# G-CU.net
KiCad netlist of a schematic drawn in EasyEDA Pro
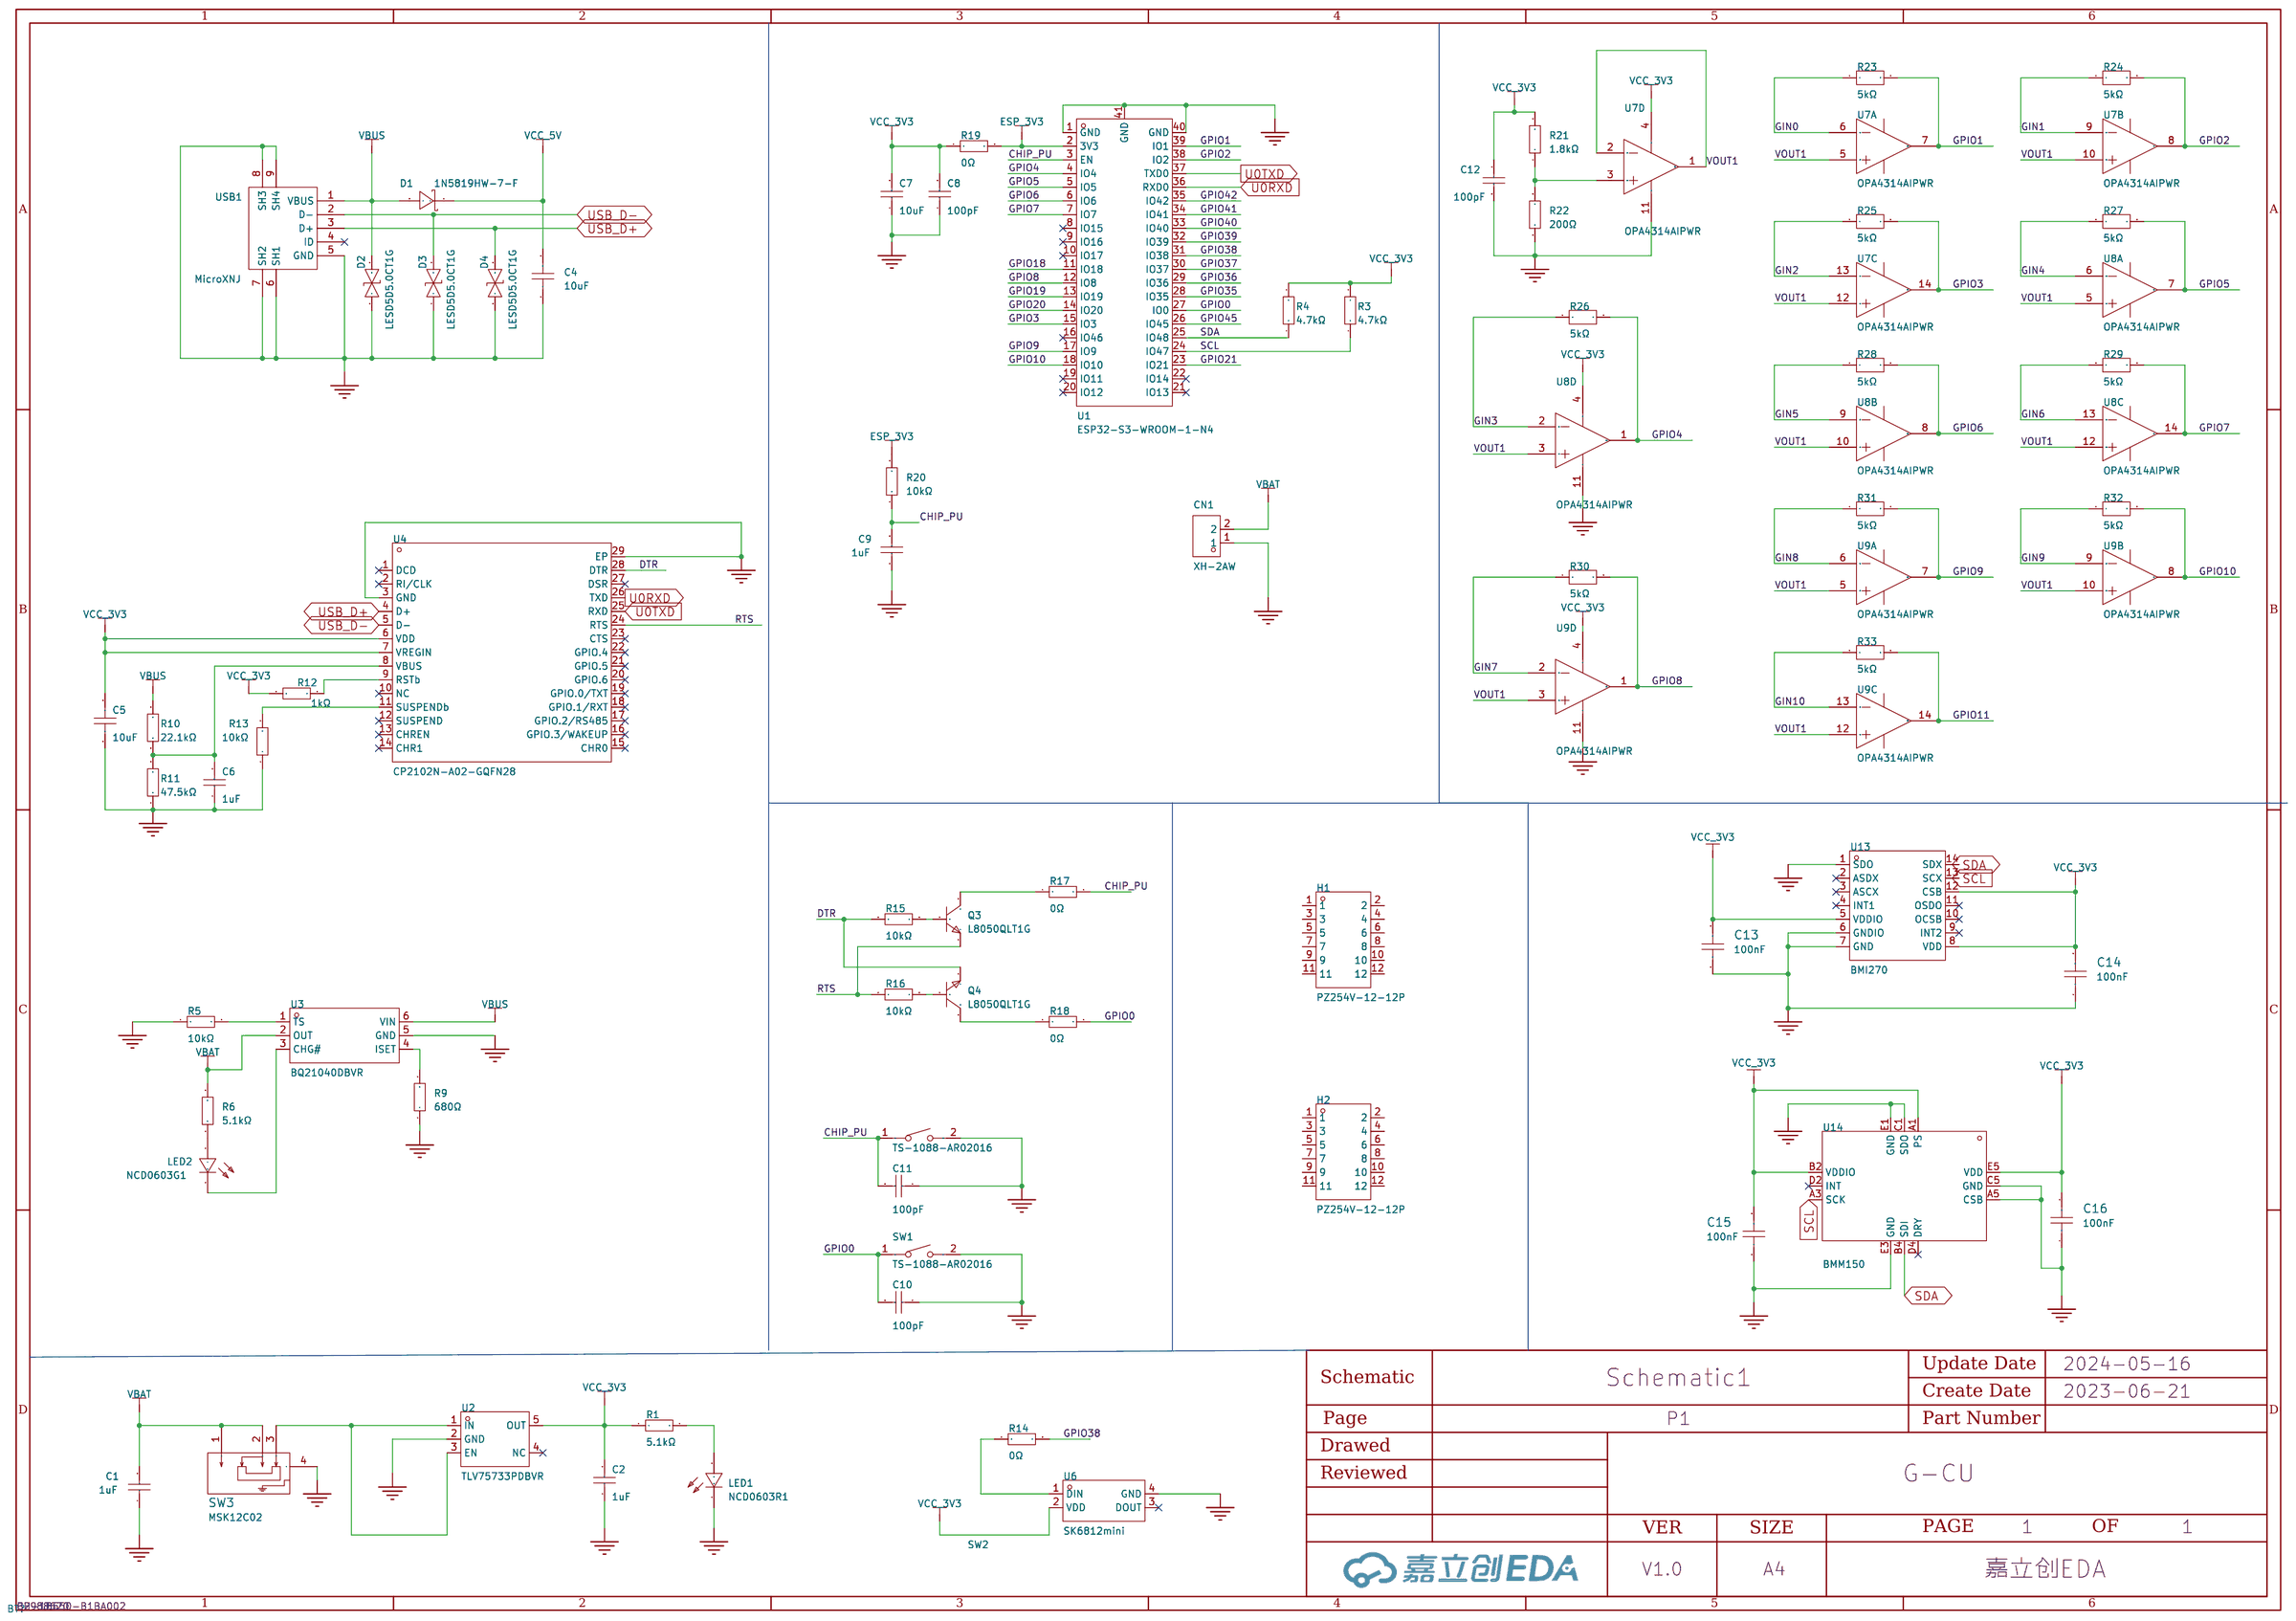
[diagram p0: schematic sheet]

(export (version "E")
  (design (tool "Eeschema 10.0.6"))
  (components
    (comp (ref "C1")
      (value "1uF")
      (footprint "easyedapro:C0402")
      (description "容值:1uF;精度:±10%;额定电压:10V;材质(温度系数):X5R;")
      (fields
        (field (name "Manufacturer Part") "CL05A105KP5NNNC")
        (field (name "Manufacturer") "SAMSUNG(三星)")
      )
      (libsource (lib "easyedapro") (part "CL05A105KP5NNNC"))
    )
    (comp (ref "C2")
      (value "1uF")
      (footprint "easyedapro:C0402")
      (description "容值:1uF;精度:±10%;额定电压:10V;材质(温度系数):X5R;")
      (fields
        (field (name "Manufacturer Part") "CL05A105KP5NNNC")
        (field (name "Manufacturer") "SAMSUNG(三星)")
      )
      (libsource (lib "easyedapro") (part "CL05A105KP5NNNC"))
    )
    (comp (ref "C4")
      (value "10uF")
      (footprint "easyedapro:C0603")
      (description "容值:10uF;精度:±20%;额定电压:25V;材质(温度系数):X5R;")
      (fields
        (field (name "Manufacturer Part") "CL10A106MA8NRNC")
        (field (name "Manufacturer") "SAMSUNG(三星)")
      )
      (libsource (lib "easyedapro") (part "CL10A106MA8NRNC"))
    )
    (comp (ref "C5")
      (value "10uF")
      (footprint "easyedapro:C0603")
      (description "容值:10uF;精度:±20%;额定电压:25V;材质(温度系数):X5R;")
      (fields
        (field (name "Manufacturer Part") "CL10A106MA8NRNC")
        (field (name "Manufacturer") "SAMSUNG(三星)")
      )
      (libsource (lib "easyedapro") (part "CL10A106MA8NRNC"))
    )
    (comp (ref "C6")
      (value "1uF")
      (footprint "easyedapro:C0603")
      (description "容值:1uF;精度:±10%;额定电压:16V;材质(温度系数):X5R;")
      (fields
        (field (name "Manufacturer Part") "CL10A105KO8NNNC")
        (field (name "Manufacturer") "SAMSUNG(三星)")
      )
      (libsource (lib "easyedapro") (part "CL10A105KO8NNNC"))
    )
    (comp (ref "C7")
      (value "10uF")
      (footprint "easyedapro:C0402")
      (description "容值:10uF;精度:±20%;额定电压:6.3V;材质(温度系数):X5R;")
      (fields
        (field (name "Manufacturer Part") "CL05A106MQ5NUNC")
        (field (name "Manufacturer") "SAMSUNG(三星)")
      )
      (libsource (lib "easyedapro") (part "CL05A106MQ5NUNC"))
    )
    (comp (ref "C8")
      (value "100pF")
      (footprint "easyedapro:C0402")
      (description "容值:100pF;精度:±5%;额定电压:50V;材质(温度系数):C0G;")
      (fields (field (name "Manufacturer Part") "0402CG101J500NT") (field (name "Manufacturer") "FH(风华)"))
      (libsource (lib "easyedapro") (part "0402CG101J500NT"))
    )
    (comp (ref "C9")
      (value "1uF")
      (footprint "easyedapro:C0402")
      (description "容值:1uF;精度:±10%;额定电压:10V;材质(温度系数):X5R;")
      (fields
        (field (name "Manufacturer Part") "CL05A105KP5NNNC")
        (field (name "Manufacturer") "SAMSUNG(三星)")
      )
      (libsource (lib "easyedapro") (part "CL05A105KP5NNNC"))
    )
    (comp (ref "C10")
      (value "100pF")
      (footprint "easyedapro:C0402")
      (description "容值:100pF;精度:±5%;额定电压:50V;材质(温度系数):C0G;")
      (fields (field (name "Manufacturer Part") "0402CG101J500NT") (field (name "Manufacturer") "FH(风华)"))
      (libsource (lib "easyedapro") (part "0402CG101J500NT"))
    )
    (comp (ref "C11")
      (value "100pF")
      (footprint "easyedapro:C0402")
      (description "容值:100pF;精度:±5%;额定电压:50V;材质(温度系数):C0G;")
      (fields (field (name "Manufacturer Part") "0402CG101J500NT") (field (name "Manufacturer") "FH(风华)"))
      (libsource (lib "easyedapro") (part "0402CG101J500NT"))
    )
    (comp (ref "C12")
      (value "100pF")
      (footprint "easyedapro:C0402")
      (description "容值:100pF;精度:±5%;额定电压:50V;材质(温度系数):C0G;")
      (fields (field (name "Manufacturer Part") "0402CG101J500NT") (field (name "Manufacturer") "FH(风华)"))
      (libsource (lib "easyedapro") (part "0402CG101J500NT"))
    )
    (comp (ref "C13")
      (value "100nF")
      (footprint "easyedapro:C0402")
      (description "容值:100nF;精度:±10%;额定电压:25V;材质(温度系数):X7R;")
      (fields
        (field (name "Manufacturer Part") "FCC0402B104K250AT")
        (field (name "Manufacturer") "FOJAN(富捷)")
      )
      (libsource (lib "easyedapro") (part "FCC0402B104K250AT"))
    )
    (comp (ref "C14")
      (value "100nF")
      (footprint "easyedapro:C0402")
      (description "容值:100nF;精度:±10%;额定电压:25V;材质(温度系数):X7R;")
      (fields
        (field (name "Manufacturer Part") "FCC0402B104K250AT")
        (field (name "Manufacturer") "FOJAN(富捷)")
      )
      (libsource (lib "easyedapro") (part "FCC0402B104K250AT"))
    )
    (comp (ref "C15")
      (value "100nF")
      (footprint "easyedapro:C0402")
      (description "容值:100nF;精度:±10%;额定电压:25V;材质(温度系数):X7R;")
      (fields
        (field (name "Manufacturer Part") "FCC0402B104K250AT")
        (field (name "Manufacturer") "FOJAN(富捷)")
      )
      (libsource (lib "easyedapro") (part "FCC0402B104K250AT"))
    )
    (comp (ref "C16")
      (value "100nF")
      (footprint "easyedapro:C0402")
      (description "容值:100nF;精度:±10%;额定电压:25V;材质(温度系数):X7R;")
      (fields
        (field (name "Manufacturer Part") "FCC0402B104K250AT")
        (field (name "Manufacturer") "FOJAN(富捷)")
      )
      (libsource (lib "easyedapro") (part "FCC0402B104K250AT"))
    )
    (comp (ref "CN1")
      (value "XH-2AW")
      (footprint "easyedapro:CONN-TH_XH-2AW_C2908611")
      (description "参考系列:XH;间距:2.54mm;插针结构:1x2P;排数:1;每排PIN数:2;行距:-;公母:公型插针;安装方式:弯插;额定电流:3A;工作温度范围:-25°C~+85°C;")
      (fields (field (name "Manufacturer") "HCTL(华灿天禄)"))
      (libsource (lib "easyedapro") (part "XH-2AW_C2908611"))
    )
    (comp (ref "D1")
      (value "1N5819HW-7-F")
      (footprint "easyedapro:SOD-123_L2.7-W1.6-LS3.7-RD")
      (description "直流反向耐压(Vr):40V;平均整流电流(Io):1A;正向压降(Vf):450mV@1A;")
      (fields (field (name "Manufacturer") "DIODES(美台)"))
      (libsource (lib "easyedapro") (part "1N5819HW-7-F"))
    )
    (comp (ref "D2")
      (value "LESD5D5.0CT1G")
      (footprint "easyedapro:SOD-523_L1.2-W0.8-LS1.6-BI")
      (description "极性:双向;反向截止电压(Vrwm):5V;击穿电压(VBR):5.6V;钳位电压(Vc)@Ipp:18.6V;")
      (fields (field (name "Manufacturer") "LRC(乐山无线电)"))
      (libsource (lib "easyedapro") (part "LESD5D5.0CT1G"))
    )
    (comp (ref "D3")
      (value "LESD5D5.0CT1G")
      (footprint "easyedapro:SOD-523_L1.2-W0.8-LS1.6-BI")
      (description "极性:双向;反向截止电压(Vrwm):5V;击穿电压(VBR):5.6V;钳位电压(Vc)@Ipp:18.6V;")
      (fields (field (name "Manufacturer") "LRC(乐山无线电)"))
      (libsource (lib "easyedapro") (part "LESD5D5.0CT1G"))
    )
    (comp (ref "D4")
      (value "LESD5D5.0CT1G")
      (footprint "easyedapro:SOD-523_L1.2-W0.8-LS1.6-BI")
      (description "极性:双向;反向截止电压(Vrwm):5V;击穿电压(VBR):5.6V;钳位电压(Vc)@Ipp:18.6V;")
      (fields (field (name "Manufacturer") "LRC(乐山无线电)"))
      (libsource (lib "easyedapro") (part "LESD5D5.0CT1G"))
    )
    (comp (ref "H1")
      (value "PZ254V-12-12P")
      (footprint "easyedapro:HDR-TH_12P-P2.54-V-M-R2-C6-S2.54")
      (fields (field (name "Manufacturer") "XFCN(兴飞)"))
      (libsource (lib "easyedapro") (part "PZ254V-12-12P"))
    )
    (comp (ref "H2")
      (value "PZ254V-12-12P")
      (footprint "easyedapro:HDR-TH_12P-P2.54-V-M-R2-C6-S2.54")
      (fields (field (name "Manufacturer") "XFCN(兴飞)"))
      (libsource (lib "easyedapro") (part "PZ254V-12-12P"))
    )
    (comp (ref "LED1")
      (value "NCD0603R1")
      (footprint "easyedapro:LED0603-RD_RED")
      (description "发光颜色:红灯;")
      (fields (field (name "Manufacturer") "国星光电"))
      (libsource (lib "easyedapro") (part "FC-DA1608HRK-620D"))
    )
    (comp (ref "LED2")
      (value "NCD0603G1")
      (footprint "easyedapro:LED0603-RD")
      (description "发光颜色:翠绿;")
      (fields (field (name "Manufacturer") "国星光电"))
      (libsource (lib "easyedapro") (part "FC-D1608UGK-520D10"))
    )
    (comp (ref "Q3")
      (value "L8050QLT1G")
      (footprint "easyedapro:SOT-23-3_L2.9-W1.3-P1.90-LS2.4-BR")
      (description "晶体管类型:NPN;集射极击穿电压(Vceo):25V;集电极电流(Ic):800mA;功率(Pd):225mW;")
      (fields (field (name "Manufacturer") "LRC(乐山无线电)"))
      (libsource (lib "easyedapro") (part "L8050QLT1G"))
    )
    (comp (ref "Q4")
      (value "L8050QLT1G")
      (footprint "easyedapro:SOT-23-3_L2.9-W1.3-P1.90-LS2.4-BR")
      (description "晶体管类型:NPN;集射极击穿电压(Vceo):25V;集电极电流(Ic):800mA;功率(Pd):225mW;")
      (fields (field (name "Manufacturer") "LRC(乐山无线电)"))
      (libsource (lib "easyedapro") (part "L8050QLT1G"))
    )
    (comp (ref "R1")
      (value "5.1kΩ")
      (footprint "easyedapro:R0402")
      (description "电阻类型:厚膜电阻;阻值:5.1kΩ;精度:±1%;功率:62.5mW;")
      (fields
        (field (name "Manufacturer Part") "0402WGF5101TCE")
        (field (name "Manufacturer") "UNI-ROYAL(厚声)")
      )
      (libsource (lib "easyedapro") (part "0402WGF5101TCE"))
    )
    (comp (ref "R3")
      (value "4.7kΩ")
      (footprint "easyedapro:R0402")
      (description "电阻类型:厚膜电阻;阻值:4.7kΩ;精度:±1%;功率:62.5mW;")
      (fields
        (field (name "Manufacturer Part") "0402WGF4701TCE")
        (field (name "Manufacturer") "UNI-ROYAL(厚声)")
      )
      (libsource (lib "easyedapro") (part "0402WGF4701TCE"))
    )
    (comp (ref "R4")
      (value "4.7kΩ")
      (footprint "easyedapro:R0402")
      (description "电阻类型:厚膜电阻;阻值:4.7kΩ;精度:±1%;功率:62.5mW;")
      (fields
        (field (name "Manufacturer Part") "0402WGF4701TCE")
        (field (name "Manufacturer") "UNI-ROYAL(厚声)")
      )
      (libsource (lib "easyedapro") (part "0402WGF4701TCE"))
    )
    (comp (ref "R5")
      (value "10kΩ")
      (footprint "easyedapro:R0402")
      (description "电阻类型:厚膜电阻;阻值:10kΩ;精度:±1%;功率:62.5mW;")
      (fields
        (field (name "Manufacturer Part") "0402WGF1002TCE")
        (field (name "Manufacturer") "UNI-ROYAL(厚声)")
      )
      (libsource (lib "easyedapro") (part "0402WGF1002TCE"))
    )
    (comp (ref "R6")
      (value "5.1kΩ")
      (footprint "easyedapro:R0402")
      (description "电阻类型:厚膜电阻;阻值:5.1kΩ;精度:±1%;功率:62.5mW;")
      (fields
        (field (name "Manufacturer Part") "0402WGF5101TCE")
        (field (name "Manufacturer") "UNI-ROYAL(厚声)")
      )
      (libsource (lib "easyedapro") (part "0402WGF5101TCE"))
    )
    (comp (ref "R9")
      (value "680Ω")
      (footprint "easyedapro:R0402")
      (description "电阻类型:厚膜电阻;阻值:680Ω;精度:±1%;功率:62.5mW;")
      (fields
        (field (name "Manufacturer Part") "0402WGF6800TCE")
        (field (name "Manufacturer") "UNI-ROYAL(厚声)")
      )
      (libsource (lib "easyedapro") (part "0402WGF6800TCE"))
    )
    (comp (ref "R10")
      (value "22.1kΩ")
      (footprint "easyedapro:R0402")
      (description "电阻类型:厚膜电阻;阻值:22.1kΩ;精度:±1%;功率:62.5mW;")
      (fields
        (field (name "Manufacturer Part") "0402WGF2212TCE")
        (field (name "Manufacturer") "UNI-ROYAL(厚声)")
      )
      (libsource (lib "easyedapro") (part "0402WGF2212TCE"))
    )
    (comp (ref "R11")
      (value "47.5kΩ")
      (footprint "easyedapro:R0402")
      (description "电阻类型:厚膜电阻;阻值:47.5kΩ;精度:±1%;功率:62.5mW;")
      (fields
        (field (name "Manufacturer Part") "0402WGF4752TCE")
        (field (name "Manufacturer") "UNI-ROYAL(厚声)")
      )
      (libsource (lib "easyedapro") (part "0402WGF4752TCE"))
    )
    (comp (ref "R12")
      (value "1kΩ")
      (footprint "easyedapro:R0402")
      (description "电阻类型:厚膜电阻;阻值:1kΩ;精度:±1%;功率:62.5mW;")
      (fields
        (field (name "Manufacturer Part") "0402WGF1001TCE")
        (field (name "Manufacturer") "UNI-ROYAL(厚声)")
      )
      (libsource (lib "easyedapro") (part "0402WGF1001TCE"))
    )
    (comp (ref "R13")
      (value "10kΩ")
      (footprint "easyedapro:R0402")
      (description "电阻类型:厚膜电阻;阻值:10kΩ;精度:±1%;功率:62.5mW;")
      (fields
        (field (name "Manufacturer Part") "0402WGF1002TCE")
        (field (name "Manufacturer") "UNI-ROYAL(厚声)")
      )
      (libsource (lib "easyedapro") (part "0402WGF1002TCE"))
    )
    (comp (ref "R14")
      (value "0Ω")
      (footprint "easyedapro:R0402")
      (description "电阻类型:厚膜电阻;阻值:0Ω;精度:±5%;功率:62.5mW;")
      (fields
        (field (name "Manufacturer Part") "0402WGJ0000TCE")
        (field (name "Manufacturer") "UNI-ROYAL(厚声)")
      )
      (libsource (lib "easyedapro") (part "0402WGJ0000TCE"))
    )
    (comp (ref "R15")
      (value "10kΩ")
      (footprint "easyedapro:R0402")
      (description "电阻类型:厚膜电阻;阻值:10kΩ;精度:±1%;功率:62.5mW;")
      (fields
        (field (name "Manufacturer Part") "0402WGF1002TCE")
        (field (name "Manufacturer") "UNI-ROYAL(厚声)")
      )
      (libsource (lib "easyedapro") (part "0402WGF1002TCE"))
    )
    (comp (ref "R16")
      (value "10kΩ")
      (footprint "easyedapro:R0402")
      (description "电阻类型:厚膜电阻;阻值:10kΩ;精度:±1%;功率:62.5mW;")
      (fields
        (field (name "Manufacturer Part") "0402WGF1002TCE")
        (field (name "Manufacturer") "UNI-ROYAL(厚声)")
      )
      (libsource (lib "easyedapro") (part "0402WGF1002TCE"))
    )
    (comp (ref "R17")
      (value "0Ω")
      (footprint "easyedapro:R0402")
      (description "电阻类型:厚膜电阻;阻值:0Ω;精度:±5%;功率:62.5mW;")
      (fields
        (field (name "Manufacturer Part") "0402WGJ0000TCE")
        (field (name "Manufacturer") "UNI-ROYAL(厚声)")
      )
      (libsource (lib "easyedapro") (part "0402WGJ0000TCE"))
    )
    (comp (ref "R18")
      (value "0Ω")
      (footprint "easyedapro:R0402")
      (description "电阻类型:厚膜电阻;阻值:0Ω;精度:±5%;功率:62.5mW;")
      (fields
        (field (name "Manufacturer Part") "0402WGJ0000TCE")
        (field (name "Manufacturer") "UNI-ROYAL(厚声)")
      )
      (libsource (lib "easyedapro") (part "0402WGJ0000TCE"))
    )
    (comp (ref "R19")
      (value "0Ω")
      (footprint "easyedapro:R0402")
      (description "电阻类型:厚膜电阻;阻值:0Ω;精度:±5%;功率:62.5mW;")
      (fields
        (field (name "Manufacturer Part") "0402WGJ0000TCE")
        (field (name "Manufacturer") "UNI-ROYAL(厚声)")
      )
      (libsource (lib "easyedapro") (part "0402WGJ0000TCE"))
    )
    (comp (ref "R20")
      (value "10kΩ")
      (footprint "easyedapro:R0402")
      (description "电阻类型:厚膜电阻;阻值:10kΩ;精度:±1%;功率:62.5mW;")
      (fields
        (field (name "Manufacturer Part") "0402WGF1002TCE")
        (field (name "Manufacturer") "UNI-ROYAL(厚声)")
      )
      (libsource (lib "easyedapro") (part "0402WGF1002TCE"))
    )
    (comp (ref "R21")
      (value "1.8kΩ")
      (footprint "easyedapro:R0402")
      (description "电阻类型:厚膜电阻;阻值:1.8kΩ;精度:±1%;功率:62.5mW;")
      (fields
        (field (name "Manufacturer Part") "0402WGF1801TCE")
        (field (name "Manufacturer") "UNI-ROYAL(厚声)")
      )
      (libsource (lib "easyedapro") (part "0402WGF1801TCE"))
    )
    (comp (ref "R22")
      (value "200Ω")
      (footprint "easyedapro:R0402")
      (description "电阻类型:厚膜电阻;阻值:200Ω;精度:±1%;功率:62.5mW;")
      (fields
        (field (name "Manufacturer Part") "0402WGF2000TCE")
        (field (name "Manufacturer") "UNI-ROYAL(厚声)")
      )
      (libsource (lib "easyedapro") (part "0402WGF2000TCE"))
    )
    (comp (ref "R23")
      (value "5kΩ")
      (footprint "easyedapro:R0603")
      (description "电阻类型:薄膜电阻;阻值:5kΩ;精度:±0.1%;功率:100mW;")
      (fields (field (name "Manufacturer Part") "AR03BTCX5001") (field (name "Manufacturer") "Viking(光颉)"))
      (libsource (lib "easyedapro") (part "AR03BTCX5001"))
    )
    (comp (ref "R24")
      (value "5kΩ")
      (footprint "easyedapro:R0603")
      (description "电阻类型:薄膜电阻;阻值:5kΩ;精度:±0.1%;功率:100mW;")
      (fields (field (name "Manufacturer Part") "AR03BTCX5001") (field (name "Manufacturer") "Viking(光颉)"))
      (libsource (lib "easyedapro") (part "AR03BTCX5001"))
    )
    (comp (ref "R25")
      (value "5kΩ")
      (footprint "easyedapro:R0603")
      (description "电阻类型:薄膜电阻;阻值:5kΩ;精度:±0.1%;功率:100mW;")
      (fields (field (name "Manufacturer Part") "AR03BTCX5001") (field (name "Manufacturer") "Viking(光颉)"))
      (libsource (lib "easyedapro") (part "AR03BTCX5001"))
    )
    (comp (ref "R26")
      (value "5kΩ")
      (footprint "easyedapro:R0603")
      (description "电阻类型:薄膜电阻;阻值:5kΩ;精度:±0.1%;功率:100mW;")
      (fields (field (name "Manufacturer Part") "AR03BTCX5001") (field (name "Manufacturer") "Viking(光颉)"))
      (libsource (lib "easyedapro") (part "AR03BTCX5001"))
    )
    (comp (ref "R27")
      (value "5kΩ")
      (footprint "easyedapro:R0603")
      (description "电阻类型:薄膜电阻;阻值:5kΩ;精度:±0.1%;功率:100mW;")
      (fields (field (name "Manufacturer Part") "AR03BTCX5001") (field (name "Manufacturer") "Viking(光颉)"))
      (libsource (lib "easyedapro") (part "AR03BTCX5001"))
    )
    (comp (ref "R28")
      (value "5kΩ")
      (footprint "easyedapro:R0603")
      (description "电阻类型:薄膜电阻;阻值:5kΩ;精度:±0.1%;功率:100mW;")
      (fields (field (name "Manufacturer Part") "AR03BTCX5001") (field (name "Manufacturer") "Viking(光颉)"))
      (libsource (lib "easyedapro") (part "AR03BTCX5001"))
    )
    (comp (ref "R29")
      (value "5kΩ")
      (footprint "easyedapro:R0603")
      (description "电阻类型:薄膜电阻;阻值:5kΩ;精度:±0.1%;功率:100mW;")
      (fields (field (name "Manufacturer Part") "AR03BTCX5001") (field (name "Manufacturer") "Viking(光颉)"))
      (libsource (lib "easyedapro") (part "AR03BTCX5001"))
    )
    (comp (ref "R30")
      (value "5kΩ")
      (footprint "easyedapro:R0603")
      (description "电阻类型:薄膜电阻;阻值:5kΩ;精度:±0.1%;功率:100mW;")
      (fields (field (name "Manufacturer Part") "AR03BTCX5001") (field (name "Manufacturer") "Viking(光颉)"))
      (libsource (lib "easyedapro") (part "AR03BTCX5001"))
    )
    (comp (ref "R31")
      (value "5kΩ")
      (footprint "easyedapro:R0603")
      (description "电阻类型:薄膜电阻;阻值:5kΩ;精度:±0.1%;功率:100mW;")
      (fields (field (name "Manufacturer Part") "AR03BTCX5001") (field (name "Manufacturer") "Viking(光颉)"))
      (libsource (lib "easyedapro") (part "AR03BTCX5001"))
    )
    (comp (ref "R32")
      (value "5kΩ")
      (footprint "easyedapro:R0603")
      (description "电阻类型:薄膜电阻;阻值:5kΩ;精度:±0.1%;功率:100mW;")
      (fields (field (name "Manufacturer Part") "AR03BTCX5001") (field (name "Manufacturer") "Viking(光颉)"))
      (libsource (lib "easyedapro") (part "AR03BTCX5001"))
    )
    (comp (ref "R33")
      (value "5kΩ")
      (footprint "easyedapro:R0603")
      (description "电阻类型:薄膜电阻;阻值:5kΩ;精度:±0.1%;功率:100mW;")
      (fields (field (name "Manufacturer Part") "AR03BTCX5001") (field (name "Manufacturer") "Viking(光颉)"))
      (libsource (lib "easyedapro") (part "AR03BTCX5001"))
    )
    (comp (ref "SW1")
      (value "TS-1088-AR02016")
      (footprint "easyedapro:SW-SMD_L3.9-W3.0-P4.45")
      (description "触点电流:50mA;额定电压(DC):12V;绝缘电阻:100MΩ;电路结构:单刀单掷;安装方式:立贴;作用力:160gf@±50gf;机械寿命:10万次;带支架:否;")
      (fields (field (name "Manufacturer") "XUNPU(讯普)"))
      (libsource (lib "easyedapro") (part "TS-1088-AR02016"))
    )
    (comp (ref "SW2")
      (value "TS-1088-AR02016")
      (footprint "easyedapro:SW-SMD_L3.9-W3.0-P4.45")
      (description "触点电流:50mA;额定电压(DC):12V;绝缘电阻:100MΩ;电路结构:单刀单掷;安装方式:立贴;作用力:160gf@±50gf;机械寿命:10万次;带支架:否;")
      (fields (field (name "Manufacturer") "XUNPU(讯普)"))
      (libsource (lib "easyedapro") (part "TS-1088-AR02016"))
    )
    (comp (ref "SW3")
      (value "MSK12C02")
      (footprint "easyedapro:SW-TH_MSK12C02")
      (fields (field (name "Manufacturer") "SHOU HAN(首韩)"))
      (libsource (lib "easyedapro") (part "MSK12C02"))
    )
    (comp (ref "U1")
      (value "ESP32-S3-WROOM-1-N4")
      (footprint "easyedapro:WIRELM-SMD_ESP32-S3-WROOM-1")
      (fields (field (name "Manufacturer") "ESPRESSIF(乐鑫)"))
      (libsource (lib "easyedapro") (part "ESP32-S3-WROOM-1"))
    )
    (comp (ref "U2")
      (value "TLV75733PDBVR")
      (footprint "easyedapro:SOT-23-5_L2.9-W1.6-P0.95-LS2.8-BL")
      (description "输出类型:固定;输出极性:正;输出通道数:1;最大输入电压:5.5V;输出电压:3.3V;压差:475mV@(1A);输出电流:1A;电源纹波抑制比(PSRR):52dB;")
      (fields (field (name "Manufacturer") "TI(德州仪器)"))
      (libsource (lib "easyedapro") (part "TLV75733PDBVR"))
    )
    (comp (ref "U3")
      (value "BQ21040DBVR")
      (footprint "easyedapro:SOT-23-6_L2.9-W1.6-P0.95-LS2.8-BR")
      (description "电池类型:锂离子/聚合物;电池节数:1;最大充电电流:800mA;电源电压:6.45V;")
      (fields (field (name "Manufacturer") "TI(德州仪器)"))
      (libsource (lib "easyedapro") (part "BQ21040DBVR"))
    )
    (comp (ref "U4")
      (value "CP2102N-A02-GQFN28")
      (footprint "easyedapro:QFN-28_L5.0-W5.0-P0.50-TL-EP3.3")
      (fields (field (name "Manufacturer") "SILICON LABS(芯科)"))
      (libsource (lib "easyedapro") (part "CP2102N-A02-GQFN28"))
    )
    (comp (ref "U6")
      (value "SK6812mini")
      (footprint "easyedapro:LED-SMD_4P-L3.7-W3.5-P1.75-BR-SK6812MINI")
      (fields (field (name "Manufacturer") "欧思科光电"))
      (libsource (lib "easyedapro") (part "SK6812MINI"))
    )
    (comp (ref "U7")
      (value "OPA4314AIPWR")
      (footprint "easyedapro:TSSOP-14_L5.0-W4.4-P0.65-LS6.4-BL")
      (description "OPA4314 四路、3MHz、低功耗、低噪声、RRI/O、1.8V CMOS 运算放大器")
      (fields (field (name "Manufacturer") "TI(德州仪器)"))
      (libsource (lib "easyedapro") (part "OPA4314AIPWR"))
    )
    (comp (ref "U8")
      (value "OPA4314AIPWR")
      (footprint "easyedapro:TSSOP-14_L5.0-W4.4-P0.65-LS6.4-BL")
      (description "OPA4314 四路、3MHz、低功耗、低噪声、RRI/O、1.8V CMOS 运算放大器")
      (fields (field (name "Manufacturer") "TI(德州仪器)"))
      (libsource (lib "easyedapro") (part "OPA4314AIPWR"))
    )
    (comp (ref "U9")
      (value "OPA4314AIPWR")
      (footprint "easyedapro:TSSOP-14_L5.0-W4.4-P0.65-LS6.4-BL")
      (description "OPA4314 四路、3MHz、低功耗、低噪声、RRI/O、1.8V CMOS 运算放大器")
      (fields (field (name "Manufacturer") "TI(德州仪器)"))
      (libsource (lib "easyedapro") (part "OPA4314AIPWR"))
    )
    (comp (ref "U13")
      (value "BMI270")
      (footprint "easyedapro:LGA-14_L3.0-W2.5-P0.50-BR")
      (description "IMU-惯性测量单元")
      (fields (field (name "Manufacturer") "Bosch(博世)"))
      (libsource (lib "easyedapro") (part "BMI270"))
    )
    (comp (ref "U14")
      (value "BMM150")
      (footprint "easyedapro:WLCSP-12_L1.6-W1.6_BMM150")
      (description "磁传感器 3轴磁罗盘")
      (fields (field (name "Manufacturer") "Bosch(博世)"))
      (libsource (lib "easyedapro") (part "BMM150"))
    )
    (comp (ref "USB1")
      (value "MicroXNJ")
      (footprint "easyedapro:MICRO-USB-SMD_MICROXNJ")
      (description "连接器类型:Micro-B;标准:USB 2.0;公母:母座;触点数量:5;端口数量:1;安装方式:卧贴;额定电流 - 电源:1A;工作温度范围:-20°C~+85°C;")
      (fields (field (name "Manufacturer") "SHOU HAN(首韩)"))
      (libsource (lib "easyedapro") (part "MICROXNJ"))
    )
  )
  (nets
    (net (code "1") (name "/CHIP_PU") (class "Default")
      (node (ref "C11") (pin "2") (pinfunction "2_2") (pintype "input"))
      (node (ref "C9") (pin "2") (pinfunction "2_2") (pintype "input"))
      (node (ref "R17") (pin "2") (pinfunction "2_2") (pintype "input"))
      (node (ref "R20") (pin "1") (pinfunction "1_1") (pintype "input"))
      (node (ref "SW2") (pin "1") (pinfunction "1_1") (pintype "input"))
      (node (ref "U1") (pin "3") (pinfunction "EN_3") (pintype "input"))
    )
    (net (code "2") (name "/DTR") (class "Default")
      (node (ref "Q4") (pin "2") (pinfunction "E_2") (pintype "input"))
      (node (ref "R15") (pin "1") (pinfunction "1_1") (pintype "input"))
      (node (ref "U4") (pin "28") (pinfunction "DTR_28") (pintype "input"))
    )
    (net (code "3") (name "/GIN0") (class "Default")
      (node (ref "R23") (pin "1") (pinfunction "1_1") (pintype "input"))
      (node (ref "U7") (pin "6") (pinfunction "IN_B-_6") (pintype "input"))
    )
    (net (code "4") (name "/GIN1") (class "Default")
      (node (ref "R24") (pin "1") (pinfunction "1_1") (pintype "input"))
      (node (ref "U7") (pin "9") (pinfunction "IN_C-_9") (pintype "input"))
    )
    (net (code "5") (name "/GIN2") (class "Default")
      (node (ref "R25") (pin "1") (pinfunction "1_1") (pintype "input"))
      (node (ref "U7") (pin "13") (pinfunction "IN_D-_13") (pintype "input"))
    )
    (net (code "6") (name "/GIN3") (class "Default")
      (node (ref "R26") (pin "1") (pinfunction "1_1") (pintype "input"))
      (node (ref "U8") (pin "2") (pinfunction "IN_A-_2") (pintype "input"))
    )
    (net (code "7") (name "/GIN4") (class "Default")
      (node (ref "R27") (pin "1") (pinfunction "1_1") (pintype "input"))
      (node (ref "U8") (pin "6") (pinfunction "IN_B-_6") (pintype "input"))
    )
    (net (code "8") (name "/GIN5") (class "Default")
      (node (ref "R28") (pin "1") (pinfunction "1_1") (pintype "input"))
      (node (ref "U8") (pin "9") (pinfunction "IN_C-_9") (pintype "input"))
    )
    (net (code "9") (name "/GIN6") (class "Default")
      (node (ref "R29") (pin "1") (pinfunction "1_1") (pintype "input"))
      (node (ref "U8") (pin "13") (pinfunction "IN_D-_13") (pintype "input"))
    )
    (net (code "10") (name "/GIN7") (class "Default")
      (node (ref "R30") (pin "1") (pinfunction "1_1") (pintype "input"))
      (node (ref "U9") (pin "2") (pinfunction "IN_A-_2") (pintype "input"))
    )
    (net (code "11") (name "/GIN8") (class "Default")
      (node (ref "R31") (pin "1") (pinfunction "1_1") (pintype "input"))
      (node (ref "U9") (pin "6") (pinfunction "IN_B-_6") (pintype "input"))
    )
    (net (code "12") (name "/GIN9") (class "Default")
      (node (ref "R32") (pin "1") (pinfunction "1_1") (pintype "input"))
      (node (ref "U9") (pin "9") (pinfunction "IN_C-_9") (pintype "input"))
    )
    (net (code "13") (name "/GIN10") (class "Default")
      (node (ref "R33") (pin "1") (pinfunction "1_1") (pintype "input"))
      (node (ref "U9") (pin "13") (pinfunction "IN_D-_13") (pintype "input"))
    )
    (net (code "14") (name "/GPIO0") (class "Default")
      (node (ref "C10") (pin "2") (pinfunction "2_2") (pintype "input"))
      (node (ref "R18") (pin "2") (pinfunction "2_2") (pintype "input"))
      (node (ref "SW1") (pin "1") (pinfunction "1_1") (pintype "input"))
      (node (ref "U1") (pin "27") (pinfunction "IO0_27") (pintype "input"))
    )
    (net (code "15") (name "/GPIO1") (class "Default")
      (node (ref "R23") (pin "2") (pinfunction "2_2") (pintype "input"))
      (node (ref "U1") (pin "39") (pinfunction "IO1_39") (pintype "input"))
      (node (ref "U7") (pin "7") (pinfunction "OUT_B_7") (pintype "output"))
    )
    (net (code "16") (name "/GPIO2") (class "Default")
      (node (ref "R24") (pin "2") (pinfunction "2_2") (pintype "input"))
      (node (ref "U1") (pin "38") (pinfunction "IO2_38") (pintype "input"))
      (node (ref "U7") (pin "8") (pinfunction "OUT_C_8") (pintype "output"))
    )
    (net (code "17") (name "/GPIO3") (class "Default")
      (node (ref "R25") (pin "2") (pinfunction "2_2") (pintype "input"))
      (node (ref "U1") (pin "15") (pinfunction "IO3_15") (pintype "input"))
      (node (ref "U7") (pin "14") (pinfunction "OUT_D_14") (pintype "output"))
    )
    (net (code "18") (name "/GPIO4") (class "Default")
      (node (ref "R26") (pin "2") (pinfunction "2_2") (pintype "input"))
      (node (ref "U1") (pin "4") (pinfunction "IO4_4") (pintype "input"))
      (node (ref "U8") (pin "1") (pinfunction "OUT_A_1") (pintype "output"))
    )
    (net (code "19") (name "/GPIO5") (class "Default")
      (node (ref "R27") (pin "2") (pinfunction "2_2") (pintype "input"))
      (node (ref "U1") (pin "5") (pinfunction "IO5_5") (pintype "input"))
      (node (ref "U8") (pin "7") (pinfunction "OUT_B_7") (pintype "output"))
    )
    (net (code "20") (name "/GPIO6") (class "Default")
      (node (ref "R28") (pin "2") (pinfunction "2_2") (pintype "input"))
      (node (ref "U1") (pin "6") (pinfunction "IO6_6") (pintype "input"))
      (node (ref "U8") (pin "8") (pinfunction "OUT_C_8") (pintype "output"))
    )
    (net (code "21") (name "/GPIO7") (class "Default")
      (node (ref "R29") (pin "2") (pinfunction "2_2") (pintype "input"))
      (node (ref "U1") (pin "7") (pinfunction "IO7_7") (pintype "input"))
      (node (ref "U8") (pin "14") (pinfunction "OUT_D_14") (pintype "output"))
    )
    (net (code "22") (name "/GPIO8") (class "Default")
      (node (ref "R30") (pin "2") (pinfunction "2_2") (pintype "input"))
      (node (ref "U1") (pin "12") (pinfunction "IO8_12") (pintype "input"))
      (node (ref "U9") (pin "1") (pinfunction "OUT_A_1") (pintype "output"))
    )
    (net (code "23") (name "/GPIO9") (class "Default")
      (node (ref "R31") (pin "2") (pinfunction "2_2") (pintype "input"))
      (node (ref "U1") (pin "17") (pinfunction "IO9_17") (pintype "input"))
      (node (ref "U9") (pin "7") (pinfunction "OUT_B_7") (pintype "output"))
    )
    (net (code "24") (name "/GPIO10") (class "Default")
      (node (ref "R32") (pin "2") (pinfunction "2_2") (pintype "input"))
      (node (ref "U1") (pin "18") (pinfunction "IO10_18") (pintype "input"))
      (node (ref "U9") (pin "8") (pinfunction "OUT_C_8") (pintype "output"))
    )
    (net (code "25") (name "/GPIO11") (class "Default")
      (node (ref "R33") (pin "2") (pinfunction "2_2") (pintype "input"))
      (node (ref "U9") (pin "14") (pinfunction "OUT_D_14") (pintype "output"))
    )
    (net (code "26") (name "/GPIO18") (class "Default")
      (node (ref "U1") (pin "11") (pinfunction "IO18_11") (pintype "input"))
    )
    (net (code "27") (name "/GPIO19") (class "Default")
      (node (ref "U1") (pin "13") (pinfunction "IO19_13") (pintype "input"))
    )
    (net (code "28") (name "/GPIO20") (class "Default")
      (node (ref "U1") (pin "14") (pinfunction "IO20_14") (pintype "input"))
    )
    (net (code "29") (name "/GPIO21") (class "Default")
      (node (ref "U1") (pin "23") (pinfunction "IO21_23") (pintype "input"))
    )
    (net (code "30") (name "/GPIO35") (class "Default")
      (node (ref "U1") (pin "28") (pinfunction "IO35_28") (pintype "input"))
    )
    (net (code "31") (name "/GPIO36") (class "Default")
      (node (ref "U1") (pin "29") (pinfunction "IO36_29") (pintype "input"))
    )
    (net (code "32") (name "/GPIO37") (class "Default")
      (node (ref "U1") (pin "30") (pinfunction "IO37_30") (pintype "input"))
    )
    (net (code "33") (name "/GPIO38") (class "Default")
      (node (ref "R14") (pin "2") (pinfunction "2_2") (pintype "input"))
      (node (ref "U1") (pin "31") (pinfunction "IO38_31") (pintype "input"))
    )
    (net (code "34") (name "/GPIO39") (class "Default")
      (node (ref "U1") (pin "32") (pinfunction "IO39_32") (pintype "input"))
    )
    (net (code "35") (name "/GPIO40") (class "Default")
      (node (ref "U1") (pin "33") (pinfunction "IO40_33") (pintype "input"))
    )
    (net (code "36") (name "/GPIO41") (class "Default")
      (node (ref "U1") (pin "34") (pinfunction "IO41_34") (pintype "input"))
    )
    (net (code "37") (name "/GPIO42") (class "Default")
      (node (ref "U1") (pin "35") (pinfunction "IO42_35") (pintype "input"))
    )
    (net (code "38") (name "/GPIO45") (class "Default")
      (node (ref "U1") (pin "26") (pinfunction "IO45_26") (pintype "input"))
    )
    (net (code "39") (name "/RTS") (class "Default")
      (node (ref "Q3") (pin "2") (pinfunction "E_2") (pintype "input"))
      (node (ref "R16") (pin "1") (pinfunction "1_1") (pintype "input"))
      (node (ref "U4") (pin "24") (pinfunction "RTS_24") (pintype "input"))
    )
    (net (code "40") (name "/VOUT1") (class "Default")
      (node (ref "U7") (pin "1") (pinfunction "OUT_A_1") (pintype "output"))
      (node (ref "U7") (pin "10") (pinfunction "IN_C+_10") (pintype "input"))
      (node (ref "U7") (pin "12") (pinfunction "IN_D+_12") (pintype "input"))
      (node (ref "U7") (pin "2") (pinfunction "IN_A-_2") (pintype "input"))
      (node (ref "U7") (pin "5") (pinfunction "IN_B+_5") (pintype "input"))
      (node (ref "U8") (pin "10") (pinfunction "IN_C+_10") (pintype "input"))
      (node (ref "U8") (pin "12") (pinfunction "IN_D+_12") (pintype "input"))
      (node (ref "U8") (pin "3") (pinfunction "IN_A+_3") (pintype "input"))
      (node (ref "U8") (pin "5") (pinfunction "IN_B+_5") (pintype "input"))
      (node (ref "U9") (pin "10") (pinfunction "IN_C+_10") (pintype "input"))
      (node (ref "U9") (pin "12") (pinfunction "IN_D+_12") (pintype "input"))
      (node (ref "U9") (pin "3") (pinfunction "IN_A+_3") (pintype "input"))
      (node (ref "U9") (pin "5") (pinfunction "IN_B+_5") (pintype "input"))
    )
    (net (code "41") (name "ESP_3V3") (class "Default")
      (node (ref "R19") (pin "2") (pinfunction "2_2") (pintype "input"))
      (node (ref "R20") (pin "2") (pinfunction "2_2") (pintype "input"))
      (node (ref "U1") (pin "2") (pinfunction "3V3_2") (pintype "input"))
    )
    (net (code "42") (name "GND") (class "Default")
      (node (ref "C1") (pin "1") (pinfunction "1_1") (pintype "input"))
      (node (ref "C10") (pin "1") (pinfunction "1_1") (pintype "input"))
      (node (ref "C11") (pin "1") (pinfunction "1_1") (pintype "input"))
      (node (ref "C12") (pin "2") (pinfunction "2_2") (pintype "input"))
      (node (ref "C13") (pin "1") (pinfunction "1_1") (pintype "input"))
      (node (ref "C14") (pin "1") (pinfunction "1_1") (pintype "input"))
      (node (ref "C15") (pin "1") (pinfunction "1_1") (pintype "input"))
      (node (ref "C16") (pin "1") (pinfunction "1_1") (pintype "input"))
      (node (ref "C2") (pin "1") (pinfunction "1_1") (pintype "input"))
      (node (ref "C4") (pin "1") (pinfunction "1_1") (pintype "input"))
      (node (ref "C5") (pin "1") (pinfunction "1_1") (pintype "input"))
      (node (ref "C6") (pin "1") (pinfunction "1_1") (pintype "input"))
      (node (ref "C7") (pin "1") (pinfunction "1_1") (pintype "input"))
      (node (ref "C8") (pin "1") (pinfunction "1_1") (pintype "input"))
      (node (ref "C9") (pin "1") (pinfunction "1_1") (pintype "input"))
      (node (ref "CN1") (pin "1") (pinfunction "1_1") (pintype "input"))
      (node (ref "D2") (pin "1") (pinfunction "1_1") (pintype "input"))
      (node (ref "D3") (pin "1") (pinfunction "1_1") (pintype "input"))
      (node (ref "D4") (pin "1") (pinfunction "1_1") (pintype "input"))
      (node (ref "LED1") (pin "1") (pinfunction "K_1") (pintype "input"))
      (node (ref "R11") (pin "1") (pinfunction "1_1") (pintype "input"))
      (node (ref "R13") (pin "1") (pinfunction "1_1") (pintype "input"))
      (node (ref "R22") (pin "1") (pinfunction "1_1") (pintype "input"))
      (node (ref "R5") (pin "1") (pinfunction "1_1") (pintype "input"))
      (node (ref "R9") (pin "1") (pinfunction "1_1") (pintype "input"))
      (node (ref "SW1") (pin "2") (pinfunction "2_2") (pintype "input"))
      (node (ref "SW2") (pin "2") (pinfunction "2_2") (pintype "input"))
      (node (ref "SW3") (pin "4") (pinfunction "4_4") (pintype "input"))
      (node (ref "U1") (pin "1") (pinfunction "GND_1") (pintype "input"))
      (node (ref "U1") (pin "40") (pinfunction "GND_40") (pintype "input"))
      (node (ref "U1") (pin "41") (pinfunction "GND_41") (pintype "input"))
      (node (ref "U13") (pin "1") (pinfunction "SDO_1") (pintype "input"))
      (node (ref "U13") (pin "6") (pinfunction "GNDIO_6") (pintype "input"))
      (node (ref "U13") (pin "7") (pinfunction "GND_7") (pintype "input"))
      (node (ref "U14") (pin "A5") (pinfunction "CSB_A5") (pintype "input"))
      (node (ref "U14") (pin "C1") (pinfunction "SDO_C1") (pintype "input"))
      (node (ref "U14") (pin "C5") (pinfunction "GND_C5") (pintype "input"))
      (node (ref "U14") (pin "E1") (pinfunction "GND_E1") (pintype "input"))
      (node (ref "U14") (pin "E3") (pinfunction "GND_E3") (pintype "input"))
      (node (ref "U2") (pin "2") (pinfunction "GND_2") (pintype "input"))
      (node (ref "U3") (pin "5") (pinfunction "GND_5") (pintype "input"))
      (node (ref "U4") (pin "29") (pinfunction "EP_29") (pintype "input"))
      (node (ref "U4") (pin "3") (pinfunction "GND_3") (pintype "input"))
      (node (ref "U6") (pin "4") (pinfunction "GND_4") (pintype "input"))
      (node (ref "U7") (pin "11") (pinfunction "V-_11") (pintype "input"))
      (node (ref "U8") (pin "11") (pinfunction "V-_11") (pintype "input"))
      (node (ref "U9") (pin "11") (pinfunction "V-_11") (pintype "input"))
      (node (ref "USB1") (pin "5") (pinfunction "GND_5") (pintype "input"))
      (node (ref "USB1") (pin "6") (pinfunction "SH1_6") (pintype "input"))
      (node (ref "USB1") (pin "7") (pinfunction "SH2_7") (pintype "input"))
      (node (ref "USB1") (pin "8") (pinfunction "SH3_8") (pintype "input"))
      (node (ref "USB1") (pin "9") (pinfunction "SH4_9") (pintype "input"))
    )
    (net (code "43") (name "Net-(LED1-A)") (class "Default")
      (node (ref "LED1") (pin "2") (pinfunction "A_2") (pintype "input"))
      (node (ref "R1") (pin "2") (pinfunction "2_2") (pintype "input"))
    )
    (net (code "44") (name "Net-(LED2-A)") (class "Default")
      (node (ref "LED2") (pin "2") (pinfunction "A_2") (pintype "input"))
      (node (ref "R6") (pin "1") (pinfunction "1_1") (pintype "input"))
    )
    (net (code "45") (name "Net-(LED2-K)") (class "Default")
      (node (ref "LED2") (pin "1") (pinfunction "K_1") (pintype "input"))
      (node (ref "U3") (pin "3") (pinfunction "CHG#_3") (pintype "input"))
    )
    (net (code "46") (name "Net-(Q3-B)") (class "Default")
      (node (ref "Q3") (pin "1") (pinfunction "B_1") (pintype "input"))
      (node (ref "R15") (pin "2") (pinfunction "2_2") (pintype "input"))
    )
    (net (code "47") (name "Net-(Q3-C)") (class "Default")
      (node (ref "Q3") (pin "3") (pinfunction "C_3") (pintype "input"))
      (node (ref "R17") (pin "1") (pinfunction "1_1") (pintype "input"))
    )
    (net (code "48") (name "Net-(Q4-B)") (class "Default")
      (node (ref "Q4") (pin "1") (pinfunction "B_1") (pintype "input"))
      (node (ref "R16") (pin "2") (pinfunction "2_2") (pintype "input"))
    )
    (net (code "49") (name "Net-(Q4-C)") (class "Default")
      (node (ref "Q4") (pin "3") (pinfunction "C_3") (pintype "input"))
      (node (ref "R18") (pin "1") (pinfunction "1_1") (pintype "input"))
    )
    (net (code "50") (name "Net-(U2-EN)") (class "Default")
      (node (ref "SW3") (pin "3") (pinfunction "3_3") (pintype "input"))
      (node (ref "U2") (pin "1") (pinfunction "IN_1") (pintype "input"))
      (node (ref "U2") (pin "3") (pinfunction "EN_3") (pintype "input"))
    )
    (net (code "51") (name "Net-(U3-ISET)") (class "Default")
      (node (ref "R9") (pin "2") (pinfunction "2_2") (pintype "input"))
      (node (ref "U3") (pin "4") (pinfunction "ISET_4") (pintype "input"))
    )
    (net (code "52") (name "Net-(U3-TS)") (class "Default")
      (node (ref "R5") (pin "2") (pinfunction "2_2") (pintype "input"))
      (node (ref "U3") (pin "1") (pinfunction "TS_1") (pintype "input"))
    )
    (net (code "53") (name "Net-(U4-RSTb)") (class "Default")
      (node (ref "R12") (pin "1") (pinfunction "1_1") (pintype "input"))
      (node (ref "U4") (pin "9") (pinfunction "RSTb_9") (pintype "input"))
    )
    (net (code "54") (name "Net-(U4-SUSPENDb)") (class "Default")
      (node (ref "R13") (pin "2") (pinfunction "2_2") (pintype "input"))
      (node (ref "U4") (pin "11") (pinfunction "SUSPENDb_11") (pintype "input"))
    )
    (net (code "55") (name "Net-(U4-VBUS)") (class "Default")
      (node (ref "C6") (pin "2") (pinfunction "2_2") (pintype "input"))
      (node (ref "R10") (pin "1") (pinfunction "1_1") (pintype "input"))
      (node (ref "R11") (pin "2") (pinfunction "2_2") (pintype "input"))
      (node (ref "U4") (pin "8") (pinfunction "VBUS_8") (pintype "input"))
    )
    (net (code "56") (name "Net-(U6-DIN)") (class "Default")
      (node (ref "R14") (pin "1") (pinfunction "1_1") (pintype "input"))
      (node (ref "U6") (pin "1") (pinfunction "DIN_1") (pintype "input"))
    )
    (net (code "57") (name "Net-(U7D-IN_A+)") (class "Default")
      (node (ref "R21") (pin "1") (pinfunction "1_1") (pintype "input"))
      (node (ref "R22") (pin "2") (pinfunction "2_2") (pintype "input"))
      (node (ref "U7") (pin "3") (pinfunction "IN_A+_3") (pintype "input"))
    )
    (net (code "58") (name "SCL") (class "Default")
      (node (ref "R3") (pin "1") (pinfunction "1_1") (pintype "input"))
      (node (ref "U1") (pin "24") (pinfunction "IO47_24") (pintype "input"))
      (node (ref "U13") (pin "13") (pinfunction "SCX_13") (pintype "input"))
      (node (ref "U14") (pin "A3") (pinfunction "SCK_A3") (pintype "input"))
    )
    (net (code "59") (name "SDA") (class "Default")
      (node (ref "R4") (pin "1") (pinfunction "1_1") (pintype "input"))
      (node (ref "U1") (pin "25") (pinfunction "IO48_25") (pintype "input"))
      (node (ref "U13") (pin "14") (pinfunction "SDX_14") (pintype "input"))
      (node (ref "U14") (pin "B4") (pinfunction "SDI_B4") (pintype "input"))
    )
    (net (code "60") (name "U0RXD") (class "Default")
      (node (ref "U1") (pin "36") (pinfunction "RXD0_36") (pintype "input"))
      (node (ref "U4") (pin "26") (pinfunction "TXD_26") (pintype "input"))
    )
    (net (code "61") (name "U0TXD") (class "Default")
      (node (ref "U1") (pin "37") (pinfunction "TXD0_37") (pintype "input"))
      (node (ref "U4") (pin "25") (pinfunction "RXD_25") (pintype "input"))
    )
    (net (code "62") (name "USB_D+") (class "Default")
      (node (ref "D4") (pin "2") (pinfunction "2_2") (pintype "input"))
      (node (ref "U4") (pin "4") (pinfunction "D+_4") (pintype "input"))
      (node (ref "USB1") (pin "3") (pinfunction "D+_3") (pintype "input"))
    )
    (net (code "63") (name "USB_D-") (class "Default")
      (node (ref "D3") (pin "2") (pinfunction "2_2") (pintype "input"))
      (node (ref "U4") (pin "5") (pinfunction "D-_5") (pintype "input"))
      (node (ref "USB1") (pin "2") (pinfunction "D-_2") (pintype "input"))
    )
    (net (code "64") (name "VBAT") (class "Default")
      (node (ref "C1") (pin "2") (pinfunction "2_2") (pintype "input"))
      (node (ref "CN1") (pin "2") (pinfunction "2_2") (pintype "input"))
      (node (ref "R6") (pin "2") (pinfunction "2_2") (pintype "input"))
      (node (ref "SW3") (pin "1") (pinfunction "1_1") (pintype "input"))
      (node (ref "SW3") (pin "2") (pinfunction "2_2") (pintype "input"))
      (node (ref "U3") (pin "2") (pinfunction "OUT_2") (pintype "input"))
    )
    (net (code "65") (name "VBUS") (class "Default")
      (node (ref "D1") (pin "2") (pinfunction "A_2") (pintype "input"))
      (node (ref "D2") (pin "2") (pinfunction "2_2") (pintype "input"))
      (node (ref "R10") (pin "2") (pinfunction "2_2") (pintype "input"))
      (node (ref "U3") (pin "6") (pinfunction "VIN_6") (pintype "input"))
      (node (ref "USB1") (pin "1") (pinfunction "VBUS_1") (pintype "input"))
    )
    (net (code "66") (name "VCC_3V3") (class "Default")
      (node (ref "C12") (pin "1") (pinfunction "1_1") (pintype "input"))
      (node (ref "C13") (pin "2") (pinfunction "2_2") (pintype "input"))
      (node (ref "C14") (pin "2") (pinfunction "2_2") (pintype "input"))
      (node (ref "C15") (pin "2") (pinfunction "2_2") (pintype "input"))
      (node (ref "C16") (pin "2") (pinfunction "2_2") (pintype "input"))
      (node (ref "C2") (pin "2") (pinfunction "2_2") (pintype "input"))
      (node (ref "C5") (pin "2") (pinfunction "2_2") (pintype "input"))
      (node (ref "C7") (pin "2") (pinfunction "2_2") (pintype "input"))
      (node (ref "C8") (pin "2") (pinfunction "2_2") (pintype "input"))
      (node (ref "R1") (pin "1") (pinfunction "1_1") (pintype "input"))
      (node (ref "R12") (pin "2") (pinfunction "2_2") (pintype "input"))
      (node (ref "R19") (pin "1") (pinfunction "1_1") (pintype "input"))
      (node (ref "R21") (pin "2") (pinfunction "2_2") (pintype "input"))
      (node (ref "R3") (pin "2") (pinfunction "2_2") (pintype "input"))
      (node (ref "R4") (pin "2") (pinfunction "2_2") (pintype "input"))
      (node (ref "U13") (pin "12") (pinfunction "CSB_12") (pintype "input"))
      (node (ref "U13") (pin "5") (pinfunction "VDDIO_5") (pintype "input"))
      (node (ref "U13") (pin "8") (pinfunction "VDD_8") (pintype "input"))
      (node (ref "U14") (pin "A1") (pinfunction "PS_A1") (pintype "input"))
      (node (ref "U14") (pin "B2") (pinfunction "VDDIO_B2") (pintype "input"))
      (node (ref "U14") (pin "E5") (pinfunction "VDD_E5") (pintype "input"))
      (node (ref "U2") (pin "5") (pinfunction "OUT_5") (pintype "input"))
      (node (ref "U4") (pin "6") (pinfunction "VDD_6") (pintype "input"))
      (node (ref "U4") (pin "7") (pinfunction "VREGIN_7") (pintype "input"))
      (node (ref "U6") (pin "2") (pinfunction "VDD_2") (pintype "input"))
      (node (ref "U7") (pin "4") (pinfunction "V+_4") (pintype "input"))
      (node (ref "U8") (pin "4") (pinfunction "V+_4") (pintype "input"))
      (node (ref "U9") (pin "4") (pinfunction "V+_4") (pintype "input"))
    )
    (net (code "67") (name "VCC_5V") (class "Default")
      (node (ref "C4") (pin "2") (pinfunction "2_2") (pintype "input"))
      (node (ref "D1") (pin "1") (pinfunction "K_1") (pintype "input"))
    )
    (net (code "68") (name "unconnected-(H1-Pad1)") (class "Default")
      (node (ref "H1") (pin "1") (pinfunction "1_1") (pintype "unspecified"))
    )
    (net (code "69") (name "unconnected-(H1-Pad2)") (class "Default")
      (node (ref "H1") (pin "2") (pinfunction "2_2") (pintype "unspecified"))
    )
    (net (code "70") (name "unconnected-(H1-Pad3)") (class "Default")
      (node (ref "H1") (pin "3") (pinfunction "3_3") (pintype "unspecified"))
    )
    (net (code "71") (name "unconnected-(H1-Pad4)") (class "Default")
      (node (ref "H1") (pin "4") (pinfunction "4_4") (pintype "unspecified"))
    )
    (net (code "72") (name "unconnected-(H1-Pad5)") (class "Default")
      (node (ref "H1") (pin "5") (pinfunction "5_5") (pintype "unspecified"))
    )
    (net (code "73") (name "unconnected-(H1-Pad6)") (class "Default")
      (node (ref "H1") (pin "6") (pinfunction "6_6") (pintype "unspecified"))
    )
    (net (code "74") (name "unconnected-(H1-Pad7)") (class "Default")
      (node (ref "H1") (pin "7") (pinfunction "7_7") (pintype "unspecified"))
    )
    (net (code "75") (name "unconnected-(H1-Pad8)") (class "Default")
      (node (ref "H1") (pin "8") (pinfunction "8_8") (pintype "unspecified"))
    )
    (net (code "76") (name "unconnected-(H1-Pad9)") (class "Default")
      (node (ref "H1") (pin "9") (pinfunction "9_9") (pintype "unspecified"))
    )
    (net (code "77") (name "unconnected-(H1-Pad10)") (class "Default")
      (node (ref "H1") (pin "10") (pinfunction "10_10") (pintype "unspecified"))
    )
    (net (code "78") (name "unconnected-(H1-Pad11)") (class "Default")
      (node (ref "H1") (pin "11") (pinfunction "11_11") (pintype "unspecified"))
    )
    (net (code "79") (name "unconnected-(H1-Pad12)") (class "Default")
      (node (ref "H1") (pin "12") (pinfunction "12_12") (pintype "unspecified"))
    )
    (net (code "80") (name "unconnected-(H2-Pad1)") (class "Default")
      (node (ref "H2") (pin "1") (pinfunction "1_1") (pintype "unspecified"))
    )
    (net (code "81") (name "unconnected-(H2-Pad2)") (class "Default")
      (node (ref "H2") (pin "2") (pinfunction "2_2") (pintype "unspecified"))
    )
    (net (code "82") (name "unconnected-(H2-Pad3)") (class "Default")
      (node (ref "H2") (pin "3") (pinfunction "3_3") (pintype "unspecified"))
    )
    (net (code "83") (name "unconnected-(H2-Pad4)") (class "Default")
      (node (ref "H2") (pin "4") (pinfunction "4_4") (pintype "unspecified"))
    )
    (net (code "84") (name "unconnected-(H2-Pad5)") (class "Default")
      (node (ref "H2") (pin "5") (pinfunction "5_5") (pintype "unspecified"))
    )
    (net (code "85") (name "unconnected-(H2-Pad6)") (class "Default")
      (node (ref "H2") (pin "6") (pinfunction "6_6") (pintype "unspecified"))
    )
    (net (code "86") (name "unconnected-(H2-Pad7)") (class "Default")
      (node (ref "H2") (pin "7") (pinfunction "7_7") (pintype "unspecified"))
    )
    (net (code "87") (name "unconnected-(H2-Pad8)") (class "Default")
      (node (ref "H2") (pin "8") (pinfunction "8_8") (pintype "unspecified"))
    )
    (net (code "88") (name "unconnected-(H2-Pad9)") (class "Default")
      (node (ref "H2") (pin "9") (pinfunction "9_9") (pintype "unspecified"))
    )
    (net (code "89") (name "unconnected-(H2-Pad10)") (class "Default")
      (node (ref "H2") (pin "10") (pinfunction "10_10") (pintype "unspecified"))
    )
    (net (code "90") (name "unconnected-(H2-Pad11)") (class "Default")
      (node (ref "H2") (pin "11") (pinfunction "11_11") (pintype "unspecified"))
    )
    (net (code "91") (name "unconnected-(H2-Pad12)") (class "Default")
      (node (ref "H2") (pin "12") (pinfunction "12_12") (pintype "unspecified"))
    )
    (net (code "92") (name "unconnected-(U1-IO11-Pad19)") (class "Default")
      (node (ref "U1") (pin "19") (pinfunction "IO11_19") (pintype "input+no_connect"))
    )
    (net (code "93") (name "unconnected-(U1-IO12-Pad20)") (class "Default")
      (node (ref "U1") (pin "20") (pinfunction "IO12_20") (pintype "input+no_connect"))
    )
    (net (code "94") (name "unconnected-(U1-IO13-Pad21)") (class "Default")
      (node (ref "U1") (pin "21") (pinfunction "IO13_21") (pintype "input+no_connect"))
    )
    (net (code "95") (name "unconnected-(U1-IO14-Pad22)") (class "Default")
      (node (ref "U1") (pin "22") (pinfunction "IO14_22") (pintype "input+no_connect"))
    )
    (net (code "96") (name "unconnected-(U1-IO15-Pad8)") (class "Default")
      (node (ref "U1") (pin "8") (pinfunction "IO15_8") (pintype "input+no_connect"))
    )
    (net (code "97") (name "unconnected-(U1-IO16-Pad9)") (class "Default")
      (node (ref "U1") (pin "9") (pinfunction "IO16_9") (pintype "input+no_connect"))
    )
    (net (code "98") (name "unconnected-(U1-IO17-Pad10)") (class "Default")
      (node (ref "U1") (pin "10") (pinfunction "IO17_10") (pintype "input+no_connect"))
    )
    (net (code "99") (name "unconnected-(U1-IO46-Pad16)") (class "Default")
      (node (ref "U1") (pin "16") (pinfunction "IO46_16") (pintype "input+no_connect"))
    )
    (net (code "100") (name "unconnected-(U2-NC-Pad4)") (class "Default")
      (node (ref "U2") (pin "4") (pinfunction "NC_4") (pintype "input+no_connect"))
    )
    (net (code "101") (name "unconnected-(U4-CHR0-Pad15)") (class "Default")
      (node (ref "U4") (pin "15") (pinfunction "CHR0_15") (pintype "input+no_connect"))
    )
    (net (code "102") (name "unconnected-(U4-CHR1-Pad14)") (class "Default")
      (node (ref "U4") (pin "14") (pinfunction "CHR1_14") (pintype "input+no_connect"))
    )
    (net (code "103") (name "unconnected-(U4-CHREN-Pad13)") (class "Default")
      (node (ref "U4") (pin "13") (pinfunction "CHREN_13") (pintype "input+no_connect"))
    )
    (net (code "104") (name "unconnected-(U4-CTS-Pad23)") (class "Default")
      (node (ref "U4") (pin "23") (pinfunction "CTS_23") (pintype "input+no_connect"))
    )
    (net (code "105") (name "unconnected-(U4-DCD-Pad1)") (class "Default")
      (node (ref "U4") (pin "1") (pinfunction "DCD_1") (pintype "input+no_connect"))
    )
    (net (code "106") (name "unconnected-(U4-DSR-Pad27)") (class "Default")
      (node (ref "U4") (pin "27") (pinfunction "DSR_27") (pintype "input+no_connect"))
    )
    (net (code "107") (name "unconnected-(U4-GPIO.0{slash}TXT-Pad19)") (class "Default")
      (node (ref "U4") (pin "19") (pinfunction "GPIO.0/TXT_19") (pintype "input+no_connect"))
    )
    (net (code "108") (name "unconnected-(U4-GPIO.1{slash}RXT-Pad18)") (class "Default")
      (node (ref "U4") (pin "18") (pinfunction "GPIO.1/RXT_18") (pintype "input+no_connect"))
    )
    (net (code "109") (name "unconnected-(U4-GPIO.2{slash}RS485-Pad17)") (class "Default")
      (node (ref "U4") (pin "17") (pinfunction "GPIO.2/RS485_17") (pintype "input+no_connect"))
    )
    (net (code "110") (name "unconnected-(U4-GPIO.3{slash}WAKEUP-Pad16)") (class "Default")
      (node (ref "U4") (pin "16") (pinfunction "GPIO.3/WAKEUP_16") (pintype "input+no_connect"))
    )
    (net (code "111") (name "unconnected-(U4-GPIO.4-Pad22)") (class "Default")
      (node (ref "U4") (pin "22") (pinfunction "GPIO.4_22") (pintype "input+no_connect"))
    )
    (net (code "112") (name "unconnected-(U4-GPIO.5-Pad21)") (class "Default")
      (node (ref "U4") (pin "21") (pinfunction "GPIO.5_21") (pintype "input+no_connect"))
    )
    (net (code "113") (name "unconnected-(U4-GPIO.6-Pad20)") (class "Default")
      (node (ref "U4") (pin "20") (pinfunction "GPIO.6_20") (pintype "input+no_connect"))
    )
    (net (code "114") (name "unconnected-(U4-NC-Pad10)") (class "Default")
      (node (ref "U4") (pin "10") (pinfunction "NC_10") (pintype "input+no_connect"))
    )
    (net (code "115") (name "unconnected-(U4-RI{slash}CLK-Pad2)") (class "Default")
      (node (ref "U4") (pin "2") (pinfunction "RI/CLK_2") (pintype "input+no_connect"))
    )
    (net (code "116") (name "unconnected-(U4-SUSPEND-Pad12)") (class "Default")
      (node (ref "U4") (pin "12") (pinfunction "SUSPEND_12") (pintype "input+no_connect"))
    )
    (net (code "117") (name "unconnected-(U6-DOUT-Pad3)") (class "Default")
      (node (ref "U6") (pin "3") (pinfunction "DOUT_3") (pintype "input+no_connect"))
    )
    (net (code "118") (name "unconnected-(U13-ASCX-Pad3)") (class "Default")
      (node (ref "U13") (pin "3") (pinfunction "ASCX_3") (pintype "input+no_connect"))
    )
    (net (code "119") (name "unconnected-(U13-ASDX-Pad2)") (class "Default")
      (node (ref "U13") (pin "2") (pinfunction "ASDX_2") (pintype "input+no_connect"))
    )
    (net (code "120") (name "unconnected-(U13-INT1-Pad4)") (class "Default")
      (node (ref "U13") (pin "4") (pinfunction "INT1_4") (pintype "input+no_connect"))
    )
    (net (code "121") (name "unconnected-(U13-INT2-Pad9)") (class "Default")
      (node (ref "U13") (pin "9") (pinfunction "INT2_9") (pintype "input+no_connect"))
    )
    (net (code "122") (name "unconnected-(U13-OCSB-Pad10)") (class "Default")
      (node (ref "U13") (pin "10") (pinfunction "OCSB_10") (pintype "input+no_connect"))
    )
    (net (code "123") (name "unconnected-(U13-OSDO-Pad11)") (class "Default")
      (node (ref "U13") (pin "11") (pinfunction "OSDO_11") (pintype "input+no_connect"))
    )
    (net (code "124") (name "unconnected-(U14-DRY-PadD4)") (class "Default")
      (node (ref "U14") (pin "D4") (pinfunction "DRY_D4") (pintype "input+no_connect"))
    )
    (net (code "125") (name "unconnected-(U14-INT-PadD2)") (class "Default")
      (node (ref "U14") (pin "D2") (pinfunction "INT_D2") (pintype "input+no_connect"))
    )
    (net (code "126") (name "unconnected-(USB1-ID-Pad4)") (class "Default")
      (node (ref "USB1") (pin "4") (pinfunction "ID_4") (pintype "input+no_connect"))
    )
  )
)
